# Sheet5.net
KiCad netlist of a schematic drawn in Altium Designer
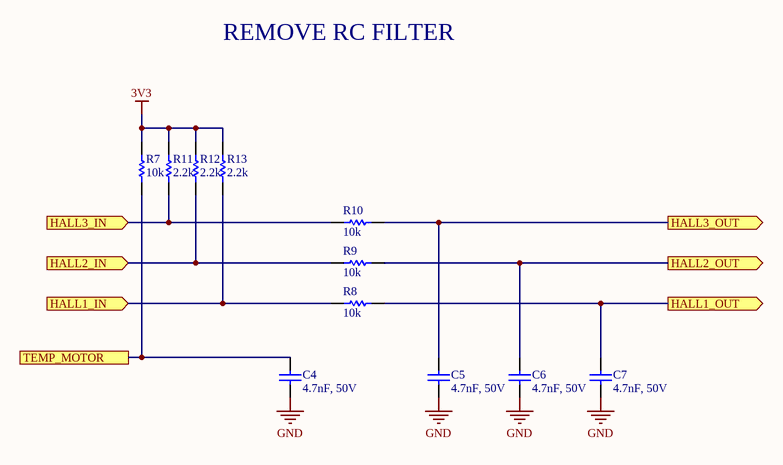
[diagram p0: Sheet5.SchDoc]

(export (version "E")
  (design (tool "Eeschema 10.0.6"))
  (components
    (comp (ref "C4")
      (value "4.7nF, 50V")
      (footprint "SMD-0603 Capacitor")
      (description "CAP 4.7n, 50V, 0603")
      (fields
        (field (name "MANUFACTURER PART NUMBER") "GRM39X472J50D")
        (field (name "MANUFACTURER") "Murata Electronics North America")
      )
      (libsource (lib "Master Data Link") (part "CAP"))
    )
    (comp (ref "C5")
      (value "4.7nF, 50V")
      (footprint "SMD-0603 Capacitor")
      (description "CAP 4.7n, 50V, 0603")
      (fields
        (field (name "MANUFACTURER PART NUMBER") "GRM39X472J50D")
        (field (name "MANUFACTURER") "Murata Electronics North America")
      )
      (libsource (lib "Master Data Link") (part "CAP"))
    )
    (comp (ref "C6")
      (value "4.7nF, 50V")
      (footprint "SMD-0603 Capacitor")
      (description "CAP 4.7n, 50V, 0603")
      (fields
        (field (name "MANUFACTURER PART NUMBER") "GRM39X472J50D")
        (field (name "MANUFACTURER") "Murata Electronics North America")
      )
      (libsource (lib "Master Data Link") (part "CAP"))
    )
    (comp (ref "C7")
      (value "4.7nF, 50V")
      (footprint "SMD-0603 Capacitor")
      (description "CAP 4.7n, 50V, 0603")
      (fields
        (field (name "MANUFACTURER PART NUMBER") "GRM39X472J50D")
        (field (name "MANUFACTURER") "Murata Electronics North America")
      )
      (libsource (lib "Master Data Link") (part "CAP"))
    )
    (comp (ref "R7")
      (value "10k")
      (footprint "SMD-0603 Resistor")
      (description "R 10k, 0603")
      (fields
        (field (name "MANUFACTURER PART NUMBER") "RK73H1JTTD1002F")
        (field (name "MANUFACTURER") "KOA Speer")
      )
      (libsource (lib "Master Data Link") (part "RES"))
    )
    (comp (ref "R8")
      (value "10k")
      (footprint "SMD-0603 Resistor")
      (description "R 10k, 0603")
      (fields
        (field (name "MANUFACTURER PART NUMBER") "RK73H1JTTD1002F")
        (field (name "MANUFACTURER") "KOA Speer")
      )
      (libsource (lib "Master Data Link") (part "RES"))
    )
    (comp (ref "R9")
      (value "10k")
      (footprint "SMD-0603 Resistor")
      (description "R 10k, 0603")
      (fields
        (field (name "MANUFACTURER PART NUMBER") "RK73H1JTTD1002F")
        (field (name "MANUFACTURER") "KOA Speer")
      )
      (libsource (lib "Master Data Link") (part "RES"))
    )
    (comp (ref "R10")
      (value "10k")
      (footprint "SMD-0603 Resistor")
      (description "R 10k, 0603")
      (fields
        (field (name "MANUFACTURER PART NUMBER") "RK73H1JTTD1002F")
        (field (name "MANUFACTURER") "KOA Speer")
      )
      (libsource (lib "Master Data Link") (part "RES"))
    )
    (comp (ref "R11")
      (value "2.2k")
      (footprint "SMD-0603 Resistor")
      (description "R 2.2k, 0603")
      (fields
        (field (name "MANUFACTURER PART NUMBER") "RK73H1JTTD2201F")
        (field (name "MANUFACTURER") "KOA Speer")
      )
      (libsource (lib "Master Data Link") (part "RES"))
    )
    (comp (ref "R12")
      (value "2.2k")
      (footprint "SMD-0603 Resistor")
      (description "R 2.2k, 0603")
      (fields
        (field (name "MANUFACTURER PART NUMBER") "RK73H1JTTD2201F")
        (field (name "MANUFACTURER") "KOA Speer")
      )
      (libsource (lib "Master Data Link") (part "RES"))
    )
    (comp (ref "R13")
      (value "2.2k")
      (footprint "SMD-0603 Resistor")
      (description "R 2.2k, 0603")
      (fields
        (field (name "MANUFACTURER PART NUMBER") "RK73H1JTTD2201F")
        (field (name "MANUFACTURER") "KOA Speer")
      )
      (libsource (lib "Master Data Link") (part "RES"))
    )
  )
  (nets
    (net (code "1") (name "/HALL1_IN") (class "Default")
      (node (ref "R13") (pin "1") (pinfunction "1_1") (pintype "passive"))
      (node (ref "R8") (pin "2") (pinfunction "2_2") (pintype "passive"))
    )
    (net (code "2") (name "/HALL1_OUT") (class "Default")
      (node (ref "C7") (pin "2") (pinfunction "2_2") (pintype "passive"))
      (node (ref "R8") (pin "1") (pinfunction "1_1") (pintype "passive"))
    )
    (net (code "3") (name "/HALL2_IN") (class "Default")
      (node (ref "R12") (pin "1") (pinfunction "1_1") (pintype "passive"))
      (node (ref "R9") (pin "2") (pinfunction "2_2") (pintype "passive"))
    )
    (net (code "4") (name "/HALL2_OUT") (class "Default")
      (node (ref "C6") (pin "2") (pinfunction "2_2") (pintype "passive"))
      (node (ref "R9") (pin "1") (pinfunction "1_1") (pintype "passive"))
    )
    (net (code "5") (name "/HALL3_IN") (class "Default")
      (node (ref "R10") (pin "2") (pinfunction "2_2") (pintype "passive"))
      (node (ref "R11") (pin "1") (pinfunction "1_1") (pintype "passive"))
    )
    (net (code "6") (name "/HALL3_OUT") (class "Default")
      (node (ref "C5") (pin "2") (pinfunction "2_2") (pintype "passive"))
      (node (ref "R10") (pin "1") (pinfunction "1_1") (pintype "passive"))
    )
    (net (code "7") (name "/TEMP_MOTOR") (class "Default")
      (node (ref "C4") (pin "2") (pinfunction "2_2") (pintype "passive"))
      (node (ref "R7") (pin "1") (pinfunction "1_1") (pintype "passive"))
    )
    (net (code "8") (name "3V3") (class "Default")
      (node (ref "R11") (pin "2") (pinfunction "2_2") (pintype "passive"))
      (node (ref "R12") (pin "2") (pinfunction "2_2") (pintype "passive"))
      (node (ref "R13") (pin "2") (pinfunction "2_2") (pintype "passive"))
      (node (ref "R7") (pin "2") (pinfunction "2_2") (pintype "passive"))
    )
    (net (code "9") (name "GND") (class "Default")
      (node (ref "C4") (pin "1") (pinfunction "1_1") (pintype "passive"))
      (node (ref "C5") (pin "1") (pinfunction "1_1") (pintype "passive"))
      (node (ref "C6") (pin "1") (pinfunction "1_1") (pintype "passive"))
      (node (ref "C7") (pin "1") (pinfunction "1_1") (pintype "passive"))
    )
  )
)
